# VCA-v2a.net
KiCad netlist of a schematic drawn in EAGLE
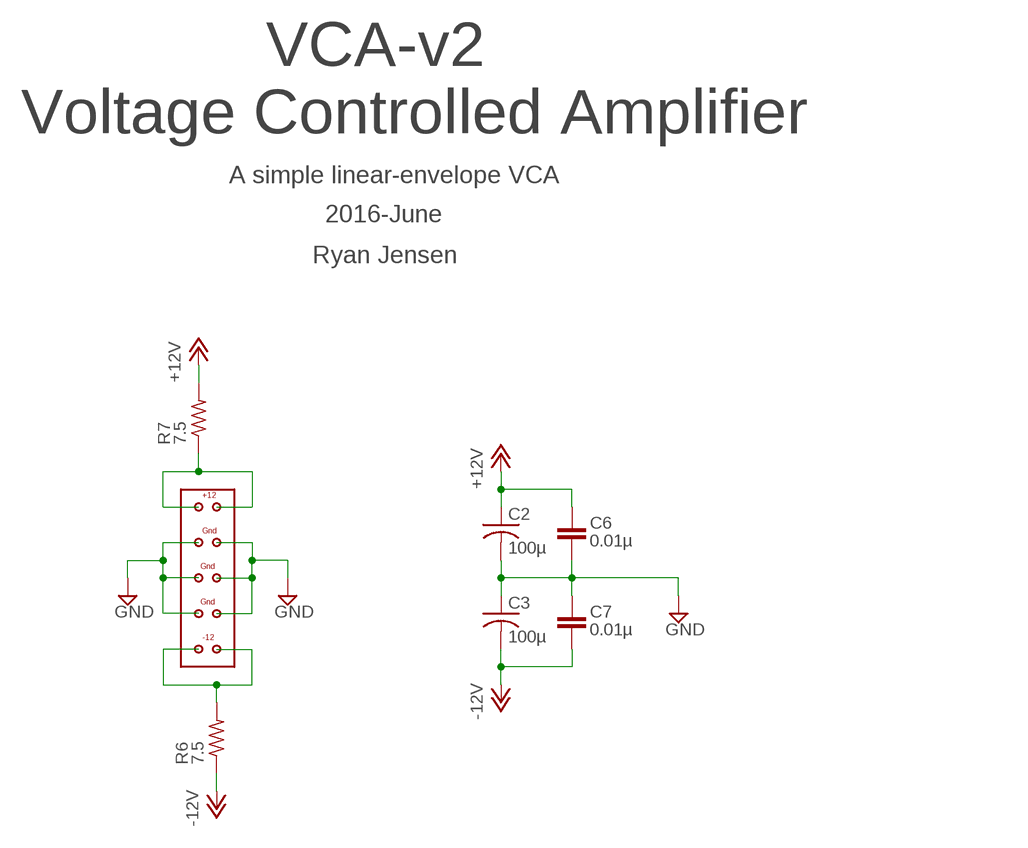
[diagram p0: schematic, sheet 1]
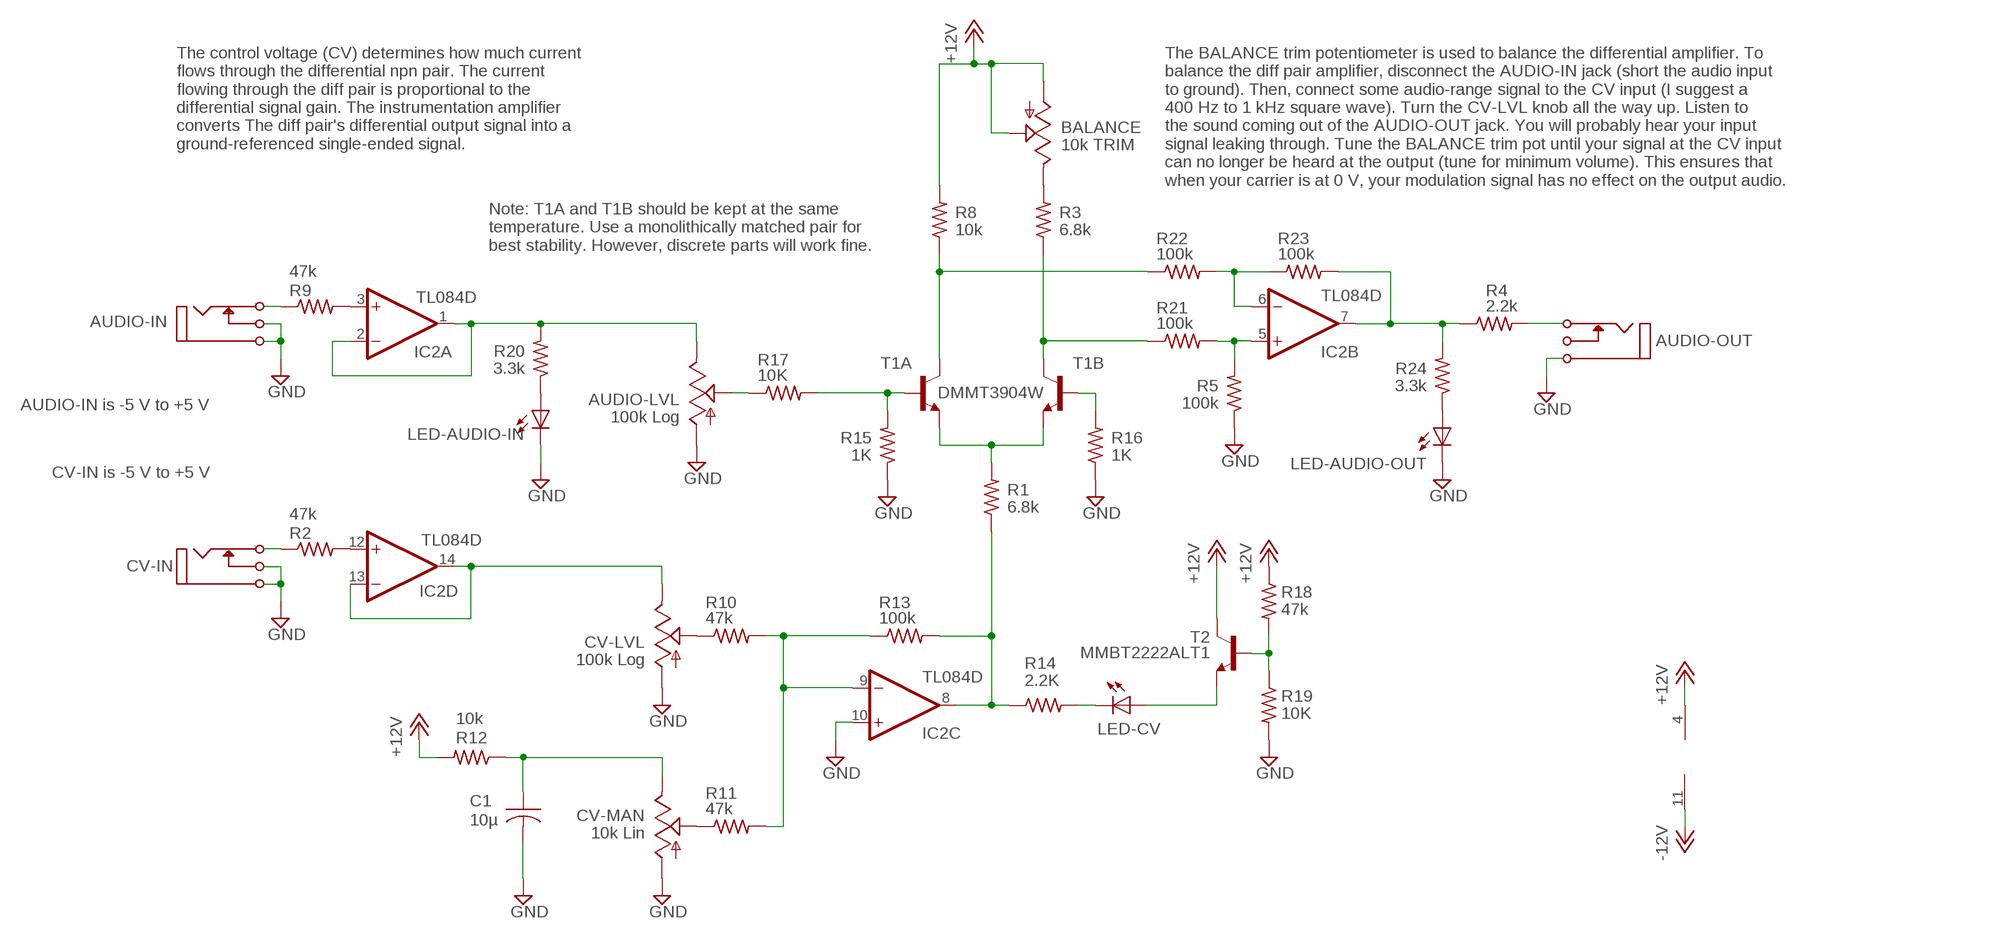
[diagram p1: schematic, sheet 2]

(export (version "E")
  (design (tool "Eeschema 10.0.6"))
  (components
    (comp (ref "C2")
      (value "100µ")
      (footprint "eagle-import:C025-050X050")
      (libsource (lib "eagle-import") (part "C-US025-050X050"))
    )
    (comp (ref "C3")
      (value "100µ")
      (footprint "eagle-import:C025-050X050")
      (libsource (lib "eagle-import") (part "C-US025-050X050"))
    )
    (comp (ref "C6")
      (value "0.01µ")
      (footprint "eagle-import:C0603")
      (libsource (lib "eagle-import") (part "C-EUC0603"))
    )
    (comp (ref "C7")
      (value "0.01µ")
      (footprint "eagle-import:C0603")
      (libsource (lib "eagle-import") (part "C-EUC0603"))
    )
    (comp (ref "R6")
      (value "7.5")
      (footprint "eagle-import:R0603")
      (libsource (lib "eagle-import") (part "R-US_R0603"))
    )
    (comp (ref "R7")
      (value "7.5")
      (footprint "eagle-import:R0603")
      (libsource (lib "eagle-import") (part "R-US_R0603"))
    )
    (comp (ref "U$1")
      (value "EURORACK-POWER")
      (footprint "eagle-import:EURORACK-POWER")
      (libsource (lib "eagle-import") (part "EURORACK-POWER"))
    )
    (comp (ref "AUDIO-IN")
      (value "I/O")
      (footprint "eagle-import:MONO_JACK")
      (libsource (lib "eagle-import") (part "MONO_JACK"))
    )
    (comp (ref "AUDIO-LVL")
      (value "100k Log")
      (footprint "eagle-import:B64Y")
      (libsource (lib "eagle-import") (part "TRIM_US-B64Y"))
    )
    (comp (ref "AUDIO-OUT")
      (value "I/O")
      (footprint "eagle-import:MONO_JACK")
      (libsource (lib "eagle-import") (part "MONO_JACK"))
    )
    (comp (ref "BALANCE")
      (value "10k TRIM")
      (footprint "eagle-import:B64Y")
      (libsource (lib "eagle-import") (part "TRIM_US-B64Y"))
    )
    (comp (ref "C1")
      (value "10µ")
      (footprint "eagle-import:C025-050X050")
      (libsource (lib "eagle-import") (part "C-US025-050X050"))
    )
    (comp (ref "CV-IN")
      (value "I/O")
      (footprint "eagle-import:MONO_JACK")
      (libsource (lib "eagle-import") (part "MONO_JACK"))
    )
    (comp (ref "CV-LVL")
      (value "100k Log")
      (footprint "eagle-import:B64Y")
      (libsource (lib "eagle-import") (part "TRIM_US-B64Y"))
    )
    (comp (ref "CV-MAN")
      (value "10k Lin")
      (footprint "eagle-import:B64Y")
      (libsource (lib "eagle-import") (part "TRIM_US-B64Y"))
    )
    (comp (ref "IC2")
      (value "TL084D")
      (footprint "eagle-import:SO14")
      (libsource (lib "eagle-import") (part "TL084D"))
    )
    (comp (ref "LED-AUDIO-IN")
      (value "TLLG4400")
      (footprint "eagle-import:LED3MM")
      (fields (field (name "MF") "VISHAY SEMICONDUCTOR"))
      (libsource (lib "eagle-import") (part "TLLG4400"))
    )
    (comp (ref "LED-AUDIO-OUT")
      (value "TLLG4400")
      (footprint "eagle-import:LED3MM")
      (fields (field (name "MF") "VISHAY SEMICONDUCTOR"))
      (libsource (lib "eagle-import") (part "TLLG4400"))
    )
    (comp (ref "LED-CV")
      (value "TLLG4400")
      (footprint "eagle-import:LED3MM")
      (fields (field (name "MF") "VISHAY SEMICONDUCTOR"))
      (libsource (lib "eagle-import") (part "TLLG4400"))
    )
    (comp (ref "R1")
      (value "6.8k")
      (footprint "eagle-import:R0603")
      (libsource (lib "eagle-import") (part "R-US_R0603"))
    )
    (comp (ref "R2")
      (value "47k")
      (footprint "eagle-import:R0603")
      (libsource (lib "eagle-import") (part "R-US_R0603"))
    )
    (comp (ref "R3")
      (value "6.8k")
      (footprint "eagle-import:R0603")
      (libsource (lib "eagle-import") (part "R-US_R0603"))
    )
    (comp (ref "R4")
      (value "2.2k")
      (footprint "eagle-import:R0603")
      (libsource (lib "eagle-import") (part "R-US_R0603"))
    )
    (comp (ref "R5")
      (value "100k")
      (footprint "eagle-import:R0603")
      (libsource (lib "eagle-import") (part "R-US_R0603"))
    )
    (comp (ref "R8")
      (value "10k")
      (footprint "eagle-import:R0603")
      (libsource (lib "eagle-import") (part "R-US_R0603"))
    )
    (comp (ref "R9")
      (value "47k")
      (footprint "eagle-import:R0603")
      (libsource (lib "eagle-import") (part "R-US_R0603"))
    )
    (comp (ref "R10")
      (value "47k")
      (footprint "eagle-import:R0603")
      (libsource (lib "eagle-import") (part "R-US_R0603"))
    )
    (comp (ref "R11")
      (value "47k")
      (footprint "eagle-import:R0603")
      (libsource (lib "eagle-import") (part "R-US_R0603"))
    )
    (comp (ref "R12")
      (value "10k")
      (footprint "eagle-import:R0603")
      (libsource (lib "eagle-import") (part "R-US_R0603"))
    )
    (comp (ref "R13")
      (value "100k")
      (footprint "eagle-import:R0603")
      (libsource (lib "eagle-import") (part "R-US_R0603"))
    )
    (comp (ref "R14")
      (value "2.2K")
      (footprint "eagle-import:R0603")
      (libsource (lib "eagle-import") (part "R-US_R0603"))
    )
    (comp (ref "R15")
      (value "1K")
      (footprint "eagle-import:R0603")
      (libsource (lib "eagle-import") (part "R-US_R0603"))
    )
    (comp (ref "R16")
      (value "1K")
      (footprint "eagle-import:R0603")
      (libsource (lib "eagle-import") (part "R-US_R0603"))
    )
    (comp (ref "R17")
      (value "10K")
      (footprint "eagle-import:R0603")
      (libsource (lib "eagle-import") (part "R-US_R0603"))
    )
    (comp (ref "R18")
      (value "47k")
      (footprint "eagle-import:R0603")
      (libsource (lib "eagle-import") (part "R-US_R0603"))
    )
    (comp (ref "R19")
      (value "10K")
      (footprint "eagle-import:R0603")
      (libsource (lib "eagle-import") (part "R-US_R0603"))
    )
    (comp (ref "R20")
      (value "3.3k")
      (footprint "eagle-import:R0603")
      (libsource (lib "eagle-import") (part "R-US_R0603"))
    )
    (comp (ref "R21")
      (value "100k")
      (footprint "eagle-import:R0603")
      (libsource (lib "eagle-import") (part "R-US_R0603"))
    )
    (comp (ref "R22")
      (value "100k")
      (footprint "eagle-import:R0603")
      (libsource (lib "eagle-import") (part "R-US_R0603"))
    )
    (comp (ref "R23")
      (value "100k")
      (footprint "eagle-import:R0603")
      (libsource (lib "eagle-import") (part "R-US_R0603"))
    )
    (comp (ref "R24")
      (value "3.3k")
      (footprint "eagle-import:R0603")
      (libsource (lib "eagle-import") (part "R-US_R0603"))
    )
    (comp (ref "T1")
      (value "DMMT3904W")
      (footprint "eagle-import:SOT363")
      (libsource (lib "eagle-import") (part "DMMT3904W"))
    )
    (comp (ref "T2")
      (value "MMBT2222ALT1")
      (footprint "eagle-import:SOT23-BEC")
      (libsource (lib "eagle-import") (part "-NPN-SOT23-BECMMBT2222ALT1"))
    )
  )
  (nets
    (net (code "1") (name "+12V") (class "Default")
      (node (ref "BALANCE") (pin "A") (pinfunction "A_A") (pintype "passive"))
      (node (ref "BALANCE") (pin "S") (pinfunction "S_S") (pintype "passive"))
      (node (ref "C2") (pin "1") (pinfunction "1_1") (pintype "passive"))
      (node (ref "C6") (pin "1") (pinfunction "1_1") (pintype "passive"))
      (node (ref "IC2") (pin "4") (pinfunction "V+_4") (pintype "power_in"))
      (node (ref "R12") (pin "2") (pinfunction "2_2") (pintype "passive"))
      (node (ref "R18") (pin "1") (pinfunction "1_1") (pintype "passive"))
      (node (ref "R7") (pin "2") (pinfunction "2_2") (pintype "passive"))
      (node (ref "R8") (pin "2") (pinfunction "2_2") (pintype "passive"))
      (node (ref "T2") (pin "C") (pinfunction "C_C") (pintype "passive"))
    )
    (net (code "2") (name "-12V") (class "Default")
      (node (ref "C3") (pin "2") (pinfunction "2_2") (pintype "passive"))
      (node (ref "C7") (pin "2") (pinfunction "2_2") (pintype "passive"))
      (node (ref "IC2") (pin "11") (pinfunction "V-_11") (pintype "power_in"))
      (node (ref "R6") (pin "1") (pinfunction "1_1") (pintype "passive"))
    )
    (net (code "3") (name "GND") (class "Default")
      (node (ref "AUDIO-IN") (pin "P$1") (pinfunction "P$1_P$1") (pintype "bidirectional"))
      (node (ref "AUDIO-IN") (pin "P$3") (pinfunction "P3_P$3") (pintype "bidirectional"))
      (node (ref "AUDIO-LVL") (pin "A") (pinfunction "A_A") (pintype "passive"))
      (node (ref "AUDIO-OUT") (pin "P$1") (pinfunction "P$1_P$1") (pintype "bidirectional"))
      (node (ref "C1") (pin "2") (pinfunction "2_2") (pintype "passive"))
      (node (ref "C2") (pin "2") (pinfunction "2_2") (pintype "passive"))
      (node (ref "C3") (pin "1") (pinfunction "1_1") (pintype "passive"))
      (node (ref "C6") (pin "2") (pinfunction "2_2") (pintype "passive"))
      (node (ref "C7") (pin "1") (pinfunction "1_1") (pintype "passive"))
      (node (ref "CV-IN") (pin "P$1") (pinfunction "P$1_P$1") (pintype "bidirectional"))
      (node (ref "CV-IN") (pin "P$3") (pinfunction "P3_P$3") (pintype "bidirectional"))
      (node (ref "CV-LVL") (pin "A") (pinfunction "A_A") (pintype "passive"))
      (node (ref "CV-MAN") (pin "A") (pinfunction "A_A") (pintype "passive"))
      (node (ref "IC2") (pin "10") (pinfunction "+IN_10") (pintype "input"))
      (node (ref "LED-AUDIO-IN") (pin "K") (pinfunction "C_K") (pintype "passive"))
      (node (ref "LED-AUDIO-OUT") (pin "K") (pinfunction "C_K") (pintype "passive"))
      (node (ref "R15") (pin "1") (pinfunction "1_1") (pintype "passive"))
      (node (ref "R16") (pin "1") (pinfunction "1_1") (pintype "passive"))
      (node (ref "R19") (pin "2") (pinfunction "2_2") (pintype "passive"))
      (node (ref "R5") (pin "1") (pinfunction "1_1") (pintype "passive"))
      (node (ref "U$1") (pin "P$3") (pinfunction "P$3_P$3") (pintype "bidirectional"))
      (node (ref "U$1") (pin "P$4") (pinfunction "P$4_P$4") (pintype "bidirectional"))
      (node (ref "U$1") (pin "P$5") (pinfunction "P$5_P$5") (pintype "bidirectional"))
      (node (ref "U$1") (pin "P$6") (pinfunction "P$6_P$6") (pintype "bidirectional"))
      (node (ref "U$1") (pin "P$7") (pinfunction "P$7_P$7") (pintype "bidirectional"))
      (node (ref "U$1") (pin "P$8") (pinfunction "P$8_P$8") (pintype "bidirectional"))
    )
    (net (code "4") (name "Net-(AUDIO-IN-P2)") (class "Default")
      (node (ref "AUDIO-IN") (pin "P$2") (pinfunction "P2_P$2") (pintype "bidirectional"))
      (node (ref "R9") (pin "1") (pinfunction "1_1") (pintype "passive"))
    )
    (net (code "5") (name "Net-(AUDIO-LVL-PadS)") (class "Default")
      (node (ref "AUDIO-LVL") (pin "S") (pinfunction "S_S") (pintype "passive"))
      (node (ref "R17") (pin "1") (pinfunction "1_1") (pintype "passive"))
    )
    (net (code "6") (name "Net-(AUDIO-OUT-P2)") (class "Default")
      (node (ref "AUDIO-OUT") (pin "P$2") (pinfunction "P2_P$2") (pintype "bidirectional"))
      (node (ref "R4") (pin "2") (pinfunction "2_2") (pintype "passive"))
    )
    (net (code "7") (name "Net-(BALANCE-PadE)") (class "Default")
      (node (ref "BALANCE") (pin "E") (pinfunction "E_E") (pintype "passive"))
      (node (ref "R3") (pin "2") (pinfunction "2_2") (pintype "passive"))
    )
    (net (code "8") (name "Net-(C1-Pad1)") (class "Default")
      (node (ref "C1") (pin "1") (pinfunction "1_1") (pintype "passive"))
      (node (ref "CV-MAN") (pin "E") (pinfunction "E_E") (pintype "passive"))
      (node (ref "R12") (pin "1") (pinfunction "1_1") (pintype "passive"))
    )
    (net (code "9") (name "Net-(CV-IN-P2)") (class "Default")
      (node (ref "CV-IN") (pin "P$2") (pinfunction "P2_P$2") (pintype "bidirectional"))
      (node (ref "R2") (pin "1") (pinfunction "1_1") (pintype "passive"))
    )
    (net (code "10") (name "Net-(CV-LVL-PadS)") (class "Default")
      (node (ref "CV-LVL") (pin "S") (pinfunction "S_S") (pintype "passive"))
      (node (ref "R10") (pin "1") (pinfunction "1_1") (pintype "passive"))
    )
    (net (code "11") (name "Net-(CV-MAN-PadS)") (class "Default")
      (node (ref "CV-MAN") (pin "S") (pinfunction "S_S") (pintype "passive"))
      (node (ref "R11") (pin "1") (pinfunction "1_1") (pintype "passive"))
    )
    (net (code "12") (name "Net-(IC2A-+IN)") (class "Default")
      (node (ref "IC2") (pin "3") (pinfunction "+IN_3") (pintype "input"))
      (node (ref "R9") (pin "2") (pinfunction "2_2") (pintype "passive"))
    )
    (net (code "13") (name "Net-(IC2A--IN)") (class "Default")
      (node (ref "AUDIO-LVL") (pin "E") (pinfunction "E_E") (pintype "passive"))
      (node (ref "IC2") (pin "1") (pinfunction "OUT_1") (pintype "output"))
      (node (ref "IC2") (pin "2") (pinfunction "-IN_2") (pintype "input"))
      (node (ref "R20") (pin "2") (pinfunction "2_2") (pintype "passive"))
    )
    (net (code "14") (name "Net-(IC2B-+IN)") (class "Default")
      (node (ref "IC2") (pin "5") (pinfunction "+IN_5") (pintype "input"))
      (node (ref "R21") (pin "2") (pinfunction "2_2") (pintype "passive"))
      (node (ref "R5") (pin "2") (pinfunction "2_2") (pintype "passive"))
    )
    (net (code "15") (name "Net-(IC2B--IN)") (class "Default")
      (node (ref "IC2") (pin "6") (pinfunction "-IN_6") (pintype "input"))
      (node (ref "R22") (pin "2") (pinfunction "2_2") (pintype "passive"))
      (node (ref "R23") (pin "1") (pinfunction "1_1") (pintype "passive"))
    )
    (net (code "16") (name "Net-(IC2B-OUT)") (class "Default")
      (node (ref "IC2") (pin "7") (pinfunction "OUT_7") (pintype "output"))
      (node (ref "R23") (pin "2") (pinfunction "2_2") (pintype "passive"))
      (node (ref "R24") (pin "2") (pinfunction "2_2") (pintype "passive"))
      (node (ref "R4") (pin "1") (pinfunction "1_1") (pintype "passive"))
    )
    (net (code "17") (name "Net-(IC2C--IN)") (class "Default")
      (node (ref "IC2") (pin "9") (pinfunction "-IN_9") (pintype "input"))
      (node (ref "R10") (pin "2") (pinfunction "2_2") (pintype "passive"))
      (node (ref "R11") (pin "2") (pinfunction "2_2") (pintype "passive"))
      (node (ref "R13") (pin "1") (pinfunction "1_1") (pintype "passive"))
    )
    (net (code "18") (name "Net-(IC2C-OUT)") (class "Default")
      (node (ref "IC2") (pin "8") (pinfunction "OUT_8") (pintype "output"))
      (node (ref "R1") (pin "1") (pinfunction "1_1") (pintype "passive"))
      (node (ref "R13") (pin "2") (pinfunction "2_2") (pintype "passive"))
      (node (ref "R14") (pin "1") (pinfunction "1_1") (pintype "passive"))
    )
    (net (code "19") (name "Net-(IC2D-+IN)") (class "Default")
      (node (ref "IC2") (pin "12") (pinfunction "+IN_12") (pintype "input"))
      (node (ref "R2") (pin "2") (pinfunction "2_2") (pintype "passive"))
    )
    (net (code "20") (name "Net-(IC2D--IN)") (class "Default")
      (node (ref "CV-LVL") (pin "E") (pinfunction "E_E") (pintype "passive"))
      (node (ref "IC2") (pin "13") (pinfunction "-IN_13") (pintype "input"))
      (node (ref "IC2") (pin "14") (pinfunction "OUT_14") (pintype "output"))
    )
    (net (code "21") (name "Net-(LED-AUDIO-IN-PadA)") (class "Default")
      (node (ref "LED-AUDIO-IN") (pin "A") (pinfunction "A_A") (pintype "passive"))
      (node (ref "R20") (pin "1") (pinfunction "1_1") (pintype "passive"))
    )
    (net (code "22") (name "Net-(LED-AUDIO-OUT-PadA)") (class "Default")
      (node (ref "LED-AUDIO-OUT") (pin "A") (pinfunction "A_A") (pintype "passive"))
      (node (ref "R24") (pin "1") (pinfunction "1_1") (pintype "passive"))
    )
    (net (code "23") (name "Net-(LED-CV-C)") (class "Default")
      (node (ref "LED-CV") (pin "K") (pinfunction "C_K") (pintype "passive"))
      (node (ref "R14") (pin "2") (pinfunction "2_2") (pintype "passive"))
    )
    (net (code "24") (name "Net-(LED-CV-PadA)") (class "Default")
      (node (ref "LED-CV") (pin "A") (pinfunction "A_A") (pintype "passive"))
      (node (ref "T2") (pin "E") (pinfunction "E_E") (pintype "passive"))
    )
    (net (code "25") (name "Net-(R6-Pad2)") (class "Default")
      (node (ref "R6") (pin "2") (pinfunction "2_2") (pintype "passive"))
      (node (ref "U$1") (pin "P$10") (pinfunction "P$10_P$10") (pintype "bidirectional"))
      (node (ref "U$1") (pin "P$9") (pinfunction "P$9_P$9") (pintype "bidirectional"))
    )
    (net (code "26") (name "Net-(R7-Pad1)") (class "Default")
      (node (ref "R7") (pin "1") (pinfunction "1_1") (pintype "passive"))
      (node (ref "U$1") (pin "P$1") (pinfunction "P$1_P$1") (pintype "bidirectional"))
      (node (ref "U$1") (pin "P$2") (pinfunction "P$2_P$2") (pintype "bidirectional"))
    )
    (net (code "27") (name "Net-(R18-Pad2)") (class "Default")
      (node (ref "R18") (pin "2") (pinfunction "2_2") (pintype "passive"))
      (node (ref "R19") (pin "1") (pinfunction "1_1") (pintype "passive"))
      (node (ref "T2") (pin "B") (pinfunction "B_B") (pintype "passive"))
    )
    (net (code "28") (name "Net-(T1A-B)") (class "Default")
      (node (ref "R15") (pin "2") (pinfunction "2_2") (pintype "passive"))
      (node (ref "R17") (pin "2") (pinfunction "2_2") (pintype "passive"))
      (node (ref "T1") (pin "1") (pinfunction "B_1") (pintype "passive"))
    )
    (net (code "29") (name "Net-(T1A-C)") (class "Default")
      (node (ref "R22") (pin "1") (pinfunction "1_1") (pintype "passive"))
      (node (ref "R8") (pin "1") (pinfunction "1_1") (pintype "passive"))
      (node (ref "T1") (pin "6") (pinfunction "C_6") (pintype "passive"))
    )
    (net (code "30") (name "Net-(T1A-E)") (class "Default")
      (node (ref "R1") (pin "2") (pinfunction "2_2") (pintype "passive"))
      (node (ref "T1") (pin "4") (pinfunction "E_4") (pintype "passive"))
      (node (ref "T1") (pin "5") (pinfunction "E_5") (pintype "passive"))
    )
    (net (code "31") (name "Net-(T1B-B)") (class "Default")
      (node (ref "R16") (pin "2") (pinfunction "2_2") (pintype "passive"))
      (node (ref "T1") (pin "2") (pinfunction "B_2") (pintype "passive"))
    )
    (net (code "32") (name "Net-(T1B-C)") (class "Default")
      (node (ref "R21") (pin "1") (pinfunction "1_1") (pintype "passive"))
      (node (ref "R3") (pin "1") (pinfunction "1_1") (pintype "passive"))
      (node (ref "T1") (pin "3") (pinfunction "C_3") (pintype "passive"))
    )
    (net (code "33") (name "unconnected-(AUDIO-OUT-P3-PadP$3)") (class "Default")
      (node (ref "AUDIO-OUT") (pin "P$3") (pinfunction "P3_P$3") (pintype "bidirectional"))
    )
  )
)
